# power.net
KiCad netlist of a schematic drawn in Altium Designer
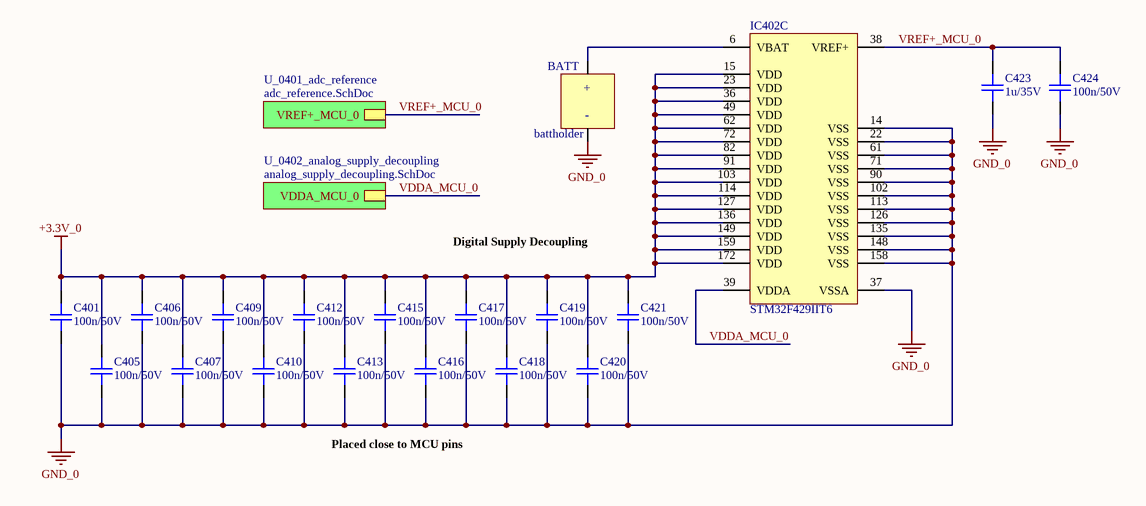
[diagram p0: power.SchDoc]

(export (version "E")
  (design (tool "Eeschema 10.0.6"))
  (components
    (comp (ref "BATT")
      (value "battholder")
      (footprint "SMTU_1225-1-LF")
      (description "SMTU 1225-1-LF, Battery Holder 1225")
      (fields
        (field (name "PART NUMBER") "Batt_Holder_SMTU_1225-1-LF")
        (field (name "MANUFACTURER") "Renata")
      )
      (libsource (lib "OE750") (part "battholder"))
    )
    (comp (ref "C401")
      (value "100n/50V")
      (footprint "CAPC1608X08N")
      (description "MLCC")
      (fields (field (name "PART NUMBER") "gen_C_ceramic_100n_50V_X7R_0603"))
      (libsource (lib "OE750") (part "C"))
    )
    (comp (ref "C405")
      (value "100n/50V")
      (footprint "CAPC1608X08N")
      (description "MLCC")
      (fields (field (name "PART NUMBER") "gen_C_ceramic_100n_50V_X7R_0603"))
      (libsource (lib "OE750") (part "C"))
    )
    (comp (ref "C406")
      (value "100n/50V")
      (footprint "CAPC1608X08N")
      (description "MLCC")
      (fields (field (name "PART NUMBER") "gen_C_ceramic_100n_50V_X7R_0603"))
      (libsource (lib "OE750") (part "C"))
    )
    (comp (ref "C407")
      (value "100n/50V")
      (footprint "CAPC1608X08N")
      (description "MLCC")
      (fields (field (name "PART NUMBER") "gen_C_ceramic_100n_50V_X7R_0603"))
      (libsource (lib "OE750") (part "C"))
    )
    (comp (ref "C409")
      (value "100n/50V")
      (footprint "CAPC1608X08N")
      (description "MLCC")
      (fields (field (name "PART NUMBER") "gen_C_ceramic_100n_50V_X7R_0603"))
      (libsource (lib "OE750") (part "C"))
    )
    (comp (ref "C410")
      (value "100n/50V")
      (footprint "CAPC1608X08N")
      (description "MLCC")
      (fields (field (name "PART NUMBER") "gen_C_ceramic_100n_50V_X7R_0603"))
      (libsource (lib "OE750") (part "C"))
    )
    (comp (ref "C412")
      (value "100n/50V")
      (footprint "CAPC1608X08N")
      (description "MLCC")
      (fields (field (name "PART NUMBER") "gen_C_ceramic_100n_50V_X7R_0603"))
      (libsource (lib "OE750") (part "C"))
    )
    (comp (ref "C413")
      (value "100n/50V")
      (footprint "CAPC1608X08N")
      (description "MLCC")
      (fields (field (name "PART NUMBER") "gen_C_ceramic_100n_50V_X7R_0603"))
      (libsource (lib "OE750") (part "C"))
    )
    (comp (ref "C415")
      (value "100n/50V")
      (footprint "CAPC1608X08N")
      (description "MLCC")
      (fields (field (name "PART NUMBER") "gen_C_ceramic_100n_50V_X7R_0603"))
      (libsource (lib "OE750") (part "C"))
    )
    (comp (ref "C416")
      (value "100n/50V")
      (footprint "CAPC1608X08N")
      (description "MLCC")
      (fields (field (name "PART NUMBER") "gen_C_ceramic_100n_50V_X7R_0603"))
      (libsource (lib "OE750") (part "C"))
    )
    (comp (ref "C417")
      (value "100n/50V")
      (footprint "CAPC1608X08N")
      (description "MLCC")
      (fields (field (name "PART NUMBER") "gen_C_ceramic_100n_50V_X7R_0603"))
      (libsource (lib "OE750") (part "C"))
    )
    (comp (ref "C418")
      (value "100n/50V")
      (footprint "CAPC1608X08N")
      (description "MLCC")
      (fields (field (name "PART NUMBER") "gen_C_ceramic_100n_50V_X7R_0603"))
      (libsource (lib "OE750") (part "C"))
    )
    (comp (ref "C419")
      (value "100n/50V")
      (footprint "CAPC1608X08N")
      (description "MLCC")
      (fields (field (name "PART NUMBER") "gen_C_ceramic_100n_50V_X7R_0603"))
      (libsource (lib "OE750") (part "C"))
    )
    (comp (ref "C420")
      (value "100n/50V")
      (footprint "CAPC1608X08N")
      (description "MLCC")
      (fields (field (name "PART NUMBER") "gen_C_ceramic_100n_50V_X7R_0603"))
      (libsource (lib "OE750") (part "C"))
    )
    (comp (ref "C421")
      (value "100n/50V")
      (footprint "CAPC1608X08N")
      (description "MLCC")
      (fields (field (name "PART NUMBER") "gen_C_ceramic_100n_50V_X7R_0603"))
      (libsource (lib "OE750") (part "C"))
    )
    (comp (ref "C423")
      (value "1u/35V")
      (footprint "CAPC1608X08N")
      (description "MLCC")
      (fields (field (name "PART NUMBER") "gen_C_ceramic_1u_35V_X7R_0603"))
      (libsource (lib "OE750") (part "C"))
    )
    (comp (ref "C424")
      (value "100n/50V")
      (footprint "CAPC1608X08N")
      (description "MLCC")
      (fields (field (name "PART NUMBER") "gen_C_ceramic_100n_50V_X7R_0603"))
      (libsource (lib "OE750") (part "C"))
    )
    (comp (ref "IC402")
      (value "STM32F429IIT6")
      (footprint "STM-LQFP176_N")
      (fields (field (name "MANUFACTURER") "STMicroelectronics"))
      (libsource (lib "Altium Content Vault") (part "MC-ARM-STM32F4X9-SQ176"))
    )
  )
  (nets
    (net (code "1") (name "+3.3V_0") (class "Default")
      (node (ref "C401") (pin "1") (pinfunction "1_1") (pintype "passive"))
      (node (ref "C405") (pin "1") (pinfunction "1_1") (pintype "passive"))
      (node (ref "C406") (pin "1") (pinfunction "1_1") (pintype "passive"))
      (node (ref "C407") (pin "1") (pinfunction "1_1") (pintype "passive"))
      (node (ref "C409") (pin "1") (pinfunction "1_1") (pintype "passive"))
      (node (ref "C410") (pin "1") (pinfunction "1_1") (pintype "passive"))
      (node (ref "C412") (pin "1") (pinfunction "1_1") (pintype "passive"))
      (node (ref "C413") (pin "1") (pinfunction "1_1") (pintype "passive"))
      (node (ref "C415") (pin "1") (pinfunction "1_1") (pintype "passive"))
      (node (ref "C416") (pin "1") (pinfunction "1_1") (pintype "passive"))
      (node (ref "C417") (pin "1") (pinfunction "1_1") (pintype "passive"))
      (node (ref "C418") (pin "1") (pinfunction "1_1") (pintype "passive"))
      (node (ref "C419") (pin "1") (pinfunction "1_1") (pintype "passive"))
      (node (ref "C420") (pin "1") (pinfunction "1_1") (pintype "passive"))
      (node (ref "C421") (pin "1") (pinfunction "1_1") (pintype "passive"))
      (node (ref "IC402") (pin "103") (pinfunction "VDD_103") (pintype "power_in"))
      (node (ref "IC402") (pin "114") (pinfunction "VDD_114") (pintype "power_in"))
      (node (ref "IC402") (pin "127") (pinfunction "VDD_127") (pintype "power_in"))
      (node (ref "IC402") (pin "136") (pinfunction "VDD_136") (pintype "power_in"))
      (node (ref "IC402") (pin "149") (pinfunction "VDD_149") (pintype "power_in"))
      (node (ref "IC402") (pin "15") (pinfunction "VDD_15") (pintype "power_in"))
      (node (ref "IC402") (pin "159") (pinfunction "VDD_159") (pintype "power_in"))
      (node (ref "IC402") (pin "172") (pinfunction "VDD_172") (pintype "power_in"))
      (node (ref "IC402") (pin "23") (pinfunction "VDD_23") (pintype "power_in"))
      (node (ref "IC402") (pin "36") (pinfunction "VDD_36") (pintype "power_in"))
      (node (ref "IC402") (pin "49") (pinfunction "VDD_49") (pintype "power_in"))
      (node (ref "IC402") (pin "62") (pinfunction "VDD_62") (pintype "power_in"))
      (node (ref "IC402") (pin "72") (pinfunction "VDD_72") (pintype "power_in"))
      (node (ref "IC402") (pin "82") (pinfunction "VDD_82") (pintype "power_in"))
      (node (ref "IC402") (pin "91") (pinfunction "VDD_91") (pintype "power_in"))
    )
    (net (code "2") (name "/VDDA_MCU_0") (class "Default")
      (node (ref "IC402") (pin "39") (pinfunction "VDDA_39") (pintype "power_in"))
    )
    (net (code "3") (name "/VREF+_MCU_0") (class "Default")
      (node (ref "C423") (pin "1") (pinfunction "1_1") (pintype "passive"))
      (node (ref "C424") (pin "1") (pinfunction "1_1") (pintype "passive"))
      (node (ref "IC402") (pin "38") (pinfunction "VREF+_38") (pintype "power_in"))
    )
    (net (code "4") (name "GND_0") (class "Default")
      (node (ref "BATT") (pin "-") (pinfunction "-_-") (pintype "passive"))
      (node (ref "C401") (pin "2") (pinfunction "2_2") (pintype "passive"))
      (node (ref "C405") (pin "2") (pinfunction "2_2") (pintype "passive"))
      (node (ref "C406") (pin "2") (pinfunction "2_2") (pintype "passive"))
      (node (ref "C407") (pin "2") (pinfunction "2_2") (pintype "passive"))
      (node (ref "C409") (pin "2") (pinfunction "2_2") (pintype "passive"))
      (node (ref "C410") (pin "2") (pinfunction "2_2") (pintype "passive"))
      (node (ref "C412") (pin "2") (pinfunction "2_2") (pintype "passive"))
      (node (ref "C413") (pin "2") (pinfunction "2_2") (pintype "passive"))
      (node (ref "C415") (pin "2") (pinfunction "2_2") (pintype "passive"))
      (node (ref "C416") (pin "2") (pinfunction "2_2") (pintype "passive"))
      (node (ref "C417") (pin "2") (pinfunction "2_2") (pintype "passive"))
      (node (ref "C418") (pin "2") (pinfunction "2_2") (pintype "passive"))
      (node (ref "C419") (pin "2") (pinfunction "2_2") (pintype "passive"))
      (node (ref "C420") (pin "2") (pinfunction "2_2") (pintype "passive"))
      (node (ref "C421") (pin "2") (pinfunction "2_2") (pintype "passive"))
      (node (ref "C423") (pin "2") (pinfunction "2_2") (pintype "passive"))
      (node (ref "C424") (pin "2") (pinfunction "2_2") (pintype "passive"))
      (node (ref "IC402") (pin "102") (pinfunction "VSS_102") (pintype "power_in"))
      (node (ref "IC402") (pin "113") (pinfunction "VSS_113") (pintype "power_in"))
      (node (ref "IC402") (pin "126") (pinfunction "VSS_126") (pintype "power_in"))
      (node (ref "IC402") (pin "135") (pinfunction "VSS_135") (pintype "power_in"))
      (node (ref "IC402") (pin "14") (pinfunction "VSS_14") (pintype "power_in"))
      (node (ref "IC402") (pin "148") (pinfunction "VSS_148") (pintype "power_in"))
      (node (ref "IC402") (pin "158") (pinfunction "VSS_158") (pintype "power_in"))
      (node (ref "IC402") (pin "22") (pinfunction "VSS_22") (pintype "power_in"))
      (node (ref "IC402") (pin "37") (pinfunction "VSSA_37") (pintype "power_in"))
      (node (ref "IC402") (pin "61") (pinfunction "VSS_61") (pintype "power_in"))
      (node (ref "IC402") (pin "71") (pinfunction "VSS_71") (pintype "power_in"))
      (node (ref "IC402") (pin "90") (pinfunction "VSS_90") (pintype "power_in"))
    )
    (net (code "5") (name "Net-(IC402C-VBAT)") (class "Default")
      (node (ref "BATT") (pin "+") (pinfunction "+_+") (pintype "passive"))
      (node (ref "IC402") (pin "6") (pinfunction "VBAT_6") (pintype "power_in"))
    )
  )
)
